# Sheet1.net
KiCad netlist of a schematic drawn in Altium Designer
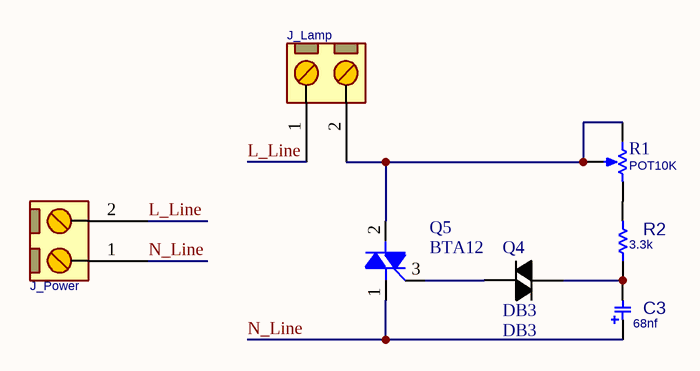
[diagram p0: Sheet1.SchDoc]

(export (version "E")
  (design (tool "Eeschema 10.0.6"))
  (components
    (comp (ref "C3")
      (value "68nf")
      (footprint "C_FLM_7X5H11")
      (description "CAP, THD, FILM,")
      (fields (field (name "MANF_P#") "MANF_PART#") (field (name "MANF") "MANF"))
      (libsource (lib "passive_thd") (part "CAP_THD_FLM"))
    )
    (comp (ref "J_Lamp")
      (value "CONN_TB2")
      (footprint "MSTB_2")
      (description "CONN, PHOENIX MSTB, 5-G, 5.08mm pitch")
      (libsource (lib "conn_terminalB") (part "CONN_MSTB_2"))
    )
    (comp (ref "J_Power")
      (value "CONN_TB2")
      (footprint "MSTB_2")
      (description "CONN, PHOENIX MSTB, 5-G, 5.08mm pitch")
      (libsource (lib "") (part "CONN_MSTB_2_1"))
    )
    (comp (ref "Q4")
      (value "DB3")
      (footprint "D_AX03_DO35")
      (description "Diac, 32VBO, DO-35")
      (fields (field (name "MANF") "ST") (field (name "ALTIUM_VALUE") "DB3"))
      (libsource (lib "triac_diac") (part "DIAC_DB3_DO35"))
    )
    (comp (ref "Q5")
      (value "BTA12")
      (footprint "TO220_3")
      (description "Triac, 600V, 12A, TO-220")
      (fields (field (name "MANF_P#") "BTA12-600BW, BTA12-600CW, BTA12-600TW") (field (name "MANF") "ST"))
      (libsource (lib "triac_diac") (part "TRIAC_BTA12-600_TO220"))
    )
    (comp (ref "R1")
      (value "POT10K")
      (footprint "VOL_R")
      (description "RESISTOR, THD, Potentiometer Volume")
      (libsource (lib "resistor_pot_trimmer") (part "RES_THD_POT_VOL"))
    )
    (comp (ref "R2")
      (value "3.3k")
      (footprint "R025W_AX04")
      (description "RESISTOR, THD")
      (fields (field (name "MANF_P#") "RK73H1ETTP4701F") (field (name "MANF") "KOA SPEER"))
      (libsource (lib "passive_thd") (part "RES_THD"))
    )
  )
  (nets
    (net (code "1") (name "/L_Line") (class "Default")
      (node (ref "J_Lamp") (pin "1") (pinfunction "1_1") (pintype "passive"))
      (node (ref "J_Power") (pin "2") (pinfunction "2_2") (pintype "passive"))
    )
    (net (code "2") (name "/N_Line") (class "Default")
      (node (ref "C3") (pin "1") (pinfunction "1_1") (pintype "passive"))
      (node (ref "J_Power") (pin "1") (pinfunction "1_1") (pintype "passive"))
      (node (ref "Q5") (pin "1") (pinfunction "T1_1") (pintype "passive"))
    )
    (net (code "3") (name "Net-(Q4-A1)") (class "Default")
      (node (ref "Q4") (pin "1") (pinfunction "A1_1") (pintype "passive"))
      (node (ref "Q5") (pin "3") (pinfunction "G_3") (pintype "passive"))
    )
    (net (code "4") (name "Net-(Q4-A2)") (class "Default")
      (node (ref "C3") (pin "2") (pinfunction "2_2") (pintype "passive"))
      (node (ref "Q4") (pin "2") (pinfunction "A2_2") (pintype "passive"))
      (node (ref "R2") (pin "1") (pinfunction "1_1") (pintype "passive"))
    )
    (net (code "5") (name "Net-(Q5-T2)") (class "Default")
      (node (ref "J_Lamp") (pin "2") (pinfunction "2_2") (pintype "passive"))
      (node (ref "Q5") (pin "2") (pinfunction "T2_2") (pintype "passive"))
      (node (ref "R1") (pin "1") (pinfunction "TOP_1") (pintype "passive"))
      (node (ref "R1") (pin "2") (pinfunction "TAP_2") (pintype "passive"))
    )
    (net (code "6") (name "Net-(R1-BOT)") (class "Default")
      (node (ref "R1") (pin "3") (pinfunction "BOT_3") (pintype "passive"))
      (node (ref "R2") (pin "2") (pinfunction "2_2") (pintype "passive"))
    )
  )
)
